# 5V_AC-DC.net
KiCad netlist of a schematic drawn in EAGLE
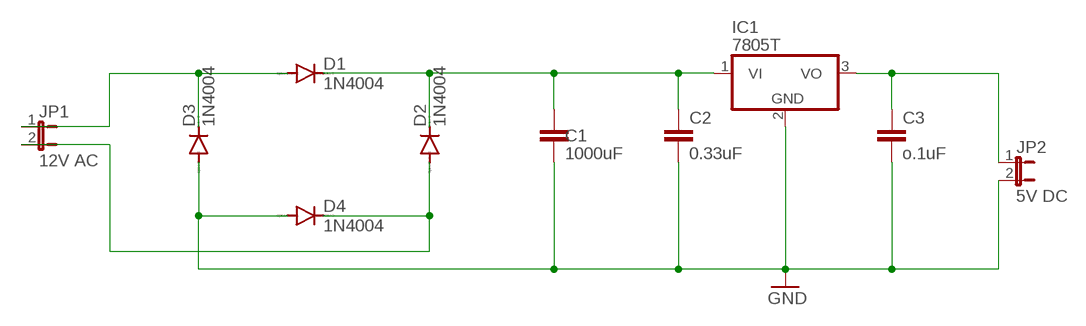
[diagram p0: schematic, sheet 1]

(export (version "E")
  (design (tool "Eeschema 10.0.6"))
  (components
    (comp (ref "C1")
      (value "1000uF")
      (footprint "eagle-import:C2.5-3")
      (libsource (lib "eagle-import") (part "C2,5-3"))
    )
    (comp (ref "C2")
      (value "0.33uF")
      (footprint "eagle-import:C2.5-3")
      (libsource (lib "eagle-import") (part "C2,5-3"))
    )
    (comp (ref "C3")
      (value "o.1uF")
      (footprint "eagle-import:C2.5-3")
      (libsource (lib "eagle-import") (part "C2,5-3"))
    )
    (comp (ref "D1")
      (value "1N4004")
      (footprint "eagle-import:DO41-10")
      (libsource (lib "eagle-import") (part "1N4004"))
    )
    (comp (ref "D2")
      (value "1N4004")
      (footprint "eagle-import:DO41-10")
      (libsource (lib "eagle-import") (part "1N4004"))
    )
    (comp (ref "D3")
      (value "1N4004")
      (footprint "eagle-import:DO41-10")
      (libsource (lib "eagle-import") (part "1N4004"))
    )
    (comp (ref "D4")
      (value "1N4004")
      (footprint "eagle-import:DO41-10")
      (libsource (lib "eagle-import") (part "1N4004"))
    )
    (comp (ref "IC1")
      (value "7805T")
      (footprint "eagle-import:TO220H")
      (libsource (lib "eagle-import") (part "78T05"))
    )
    (comp (ref "JP1")
      (value "12V AC")
      (footprint "eagle-import:JP1")
      (libsource (lib "eagle-import") (part "JP1E"))
    )
    (comp (ref "JP2")
      (value "5V DC")
      (footprint "eagle-import:JP1")
      (libsource (lib "eagle-import") (part "JP1E"))
    )
  )
  (nets
    (net (code "1") (name "GND") (class "Default")
      (node (ref "C1") (pin "2") (pinfunction "2_2") (pintype "passive"))
      (node (ref "C2") (pin "2") (pinfunction "2_2") (pintype "passive"))
      (node (ref "C3") (pin "2") (pinfunction "2_2") (pintype "passive"))
      (node (ref "D3") (pin "A") (pinfunction "A_A") (pintype "passive"))
      (node (ref "D4") (pin "A") (pinfunction "A_A") (pintype "passive"))
      (node (ref "IC1") (pin "2") (pinfunction "GND_2") (pintype "passive"))
      (node (ref "JP2") (pin "2") (pinfunction "2_2") (pintype "passive"))
    )
    (net (code "2") (name "Net-(D1-PadA)") (class "Default")
      (node (ref "D1") (pin "A") (pinfunction "A_A") (pintype "passive"))
      (node (ref "D3") (pin "C") (pinfunction "C_C") (pintype "passive"))
      (node (ref "JP1") (pin "1") (pinfunction "1_1") (pintype "passive"))
    )
    (net (code "3") (name "Net-(D2-PadA)") (class "Default")
      (node (ref "D2") (pin "A") (pinfunction "A_A") (pintype "passive"))
      (node (ref "D4") (pin "C") (pinfunction "C_C") (pintype "passive"))
      (node (ref "JP1") (pin "2") (pinfunction "2_2") (pintype "passive"))
    )
    (net (code "4") (name "Net-(IC1-VI)") (class "Default")
      (node (ref "C1") (pin "1") (pinfunction "1_1") (pintype "passive"))
      (node (ref "C2") (pin "1") (pinfunction "1_1") (pintype "passive"))
      (node (ref "D1") (pin "C") (pinfunction "C_C") (pintype "passive"))
      (node (ref "D2") (pin "C") (pinfunction "C_C") (pintype "passive"))
      (node (ref "IC1") (pin "1") (pinfunction "VI_1") (pintype "input"))
    )
    (net (code "5") (name "Net-(IC1-VO)") (class "Default")
      (node (ref "C3") (pin "1") (pinfunction "1_1") (pintype "passive"))
      (node (ref "IC1") (pin "3") (pinfunction "VO_3") (pintype "passive"))
      (node (ref "JP2") (pin "1") (pinfunction "1_1") (pintype "passive"))
    )
  )
)
